# gate_driver.net
KiCad netlist of a schematic drawn in EAGLE
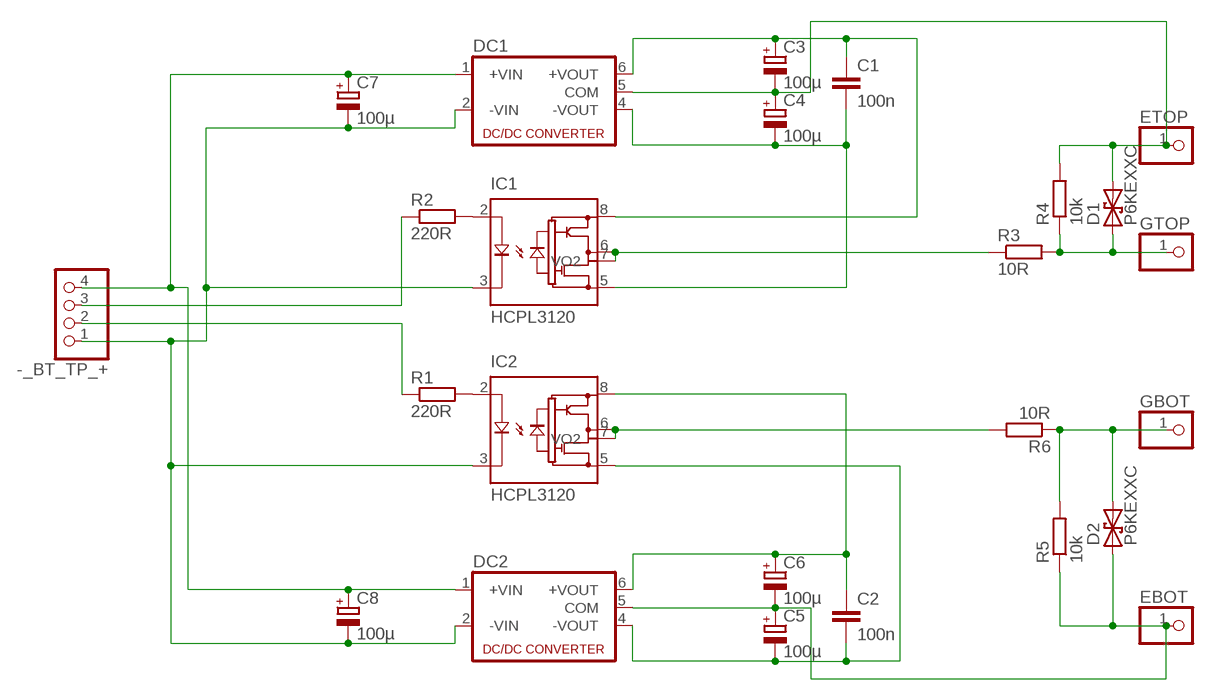
[diagram p0: schematic, sheet 1]

(export (version "E")
  (design (tool "Eeschema 10.0.6"))
  (components
    (comp (ref "-_BT_TP_+")
      (value "PINHD-1X4")
      (footprint "eagle-import:1X04")
      (libsource (lib "eagle-import") (part "PINHD-1X4"))
    )
    (comp (ref "C1")
      (value "100n")
      (footprint "eagle-import:C050-025X075")
      (libsource (lib "eagle-import") (part "C-EU050-025X075"))
    )
    (comp (ref "C2")
      (value "100n")
      (footprint "eagle-import:C050-025X075")
      (libsource (lib "eagle-import") (part "C-EU050-025X075"))
    )
    (comp (ref "C3")
      (value "100µ")
      (footprint "eagle-import:E2,5-6E")
      (libsource (lib "eagle-import") (part "CPOL-EUE2,5-6E"))
    )
    (comp (ref "C4")
      (value "100µ")
      (footprint "eagle-import:E2,5-6E")
      (libsource (lib "eagle-import") (part "CPOL-EUE2,5-6E"))
    )
    (comp (ref "C5")
      (value "100µ")
      (footprint "eagle-import:E2,5-6E")
      (libsource (lib "eagle-import") (part "CPOL-EUE2,5-6E"))
    )
    (comp (ref "C6")
      (value "100µ")
      (footprint "eagle-import:E2,5-6E")
      (libsource (lib "eagle-import") (part "CPOL-EUE2,5-6E"))
    )
    (comp (ref "C7")
      (value "100µ")
      (footprint "eagle-import:E2,5-5")
      (libsource (lib "eagle-import") (part "CPOL-EUE2.5-5"))
    )
    (comp (ref "C8")
      (value "100µ")
      (footprint "eagle-import:E2,5-5")
      (libsource (lib "eagle-import") (part "CPOL-EUE2.5-5"))
    )
    (comp (ref "D1")
      (value "P6KEXXC")
      (footprint "eagle-import:CB417-15")
      (libsource (lib "eagle-import") (part "P6KEXXC"))
    )
    (comp (ref "D2")
      (value "P6KEXXC")
      (footprint "eagle-import:CB417-15")
      (libsource (lib "eagle-import") (part "P6KEXXC"))
    )
    (comp (ref "DC1")
      (value "NMA")
      (footprint "eagle-import:NMA")
      (libsource (lib "eagle-import") (part "NMA"))
    )
    (comp (ref "DC2")
      (value "NMA")
      (footprint "eagle-import:NMA")
      (libsource (lib "eagle-import") (part "NMA"))
    )
    (comp (ref "EBOT")
      (value "PINHD-1X1")
      (footprint "eagle-import:1X01")
      (libsource (lib "eagle-import") (part "PINHD-1X1"))
    )
    (comp (ref "ETOP")
      (value "PINHD-1X1")
      (footprint "eagle-import:1X01")
      (libsource (lib "eagle-import") (part "PINHD-1X1"))
    )
    (comp (ref "GBOT")
      (value "PINHD-1X1")
      (footprint "eagle-import:1X01")
      (libsource (lib "eagle-import") (part "PINHD-1X1"))
    )
    (comp (ref "GTOP")
      (value "PINHD-1X1")
      (footprint "eagle-import:1X01")
      (libsource (lib "eagle-import") (part "PINHD-1X1"))
    )
    (comp (ref "IC1")
      (value "HCPL3120")
      (footprint "eagle-import:DIL08")
      (libsource (lib "eagle-import") (part "HCPL3120"))
    )
    (comp (ref "IC2")
      (value "HCPL3120")
      (footprint "eagle-import:DIL08")
      (libsource (lib "eagle-import") (part "HCPL3120"))
    )
    (comp (ref "R1")
      (value "220R")
      (footprint "eagle-import:0207_10")
      (libsource (lib "eagle-import") (part "R-EU_0207/10"))
    )
    (comp (ref "R2")
      (value "220R")
      (footprint "eagle-import:0207_10")
      (libsource (lib "eagle-import") (part "R-EU_0207/10"))
    )
    (comp (ref "R3")
      (value "10R")
      (footprint "eagle-import:0309_12")
      (libsource (lib "eagle-import") (part "R-EU_0309/12"))
    )
    (comp (ref "R4")
      (value "10k")
      (footprint "eagle-import:0207_10")
      (libsource (lib "eagle-import") (part "R-EU_0207/10"))
    )
    (comp (ref "R5")
      (value "10k")
      (footprint "eagle-import:0207_10")
      (libsource (lib "eagle-import") (part "R-EU_0207/10"))
    )
    (comp (ref "R6")
      (value "10R")
      (footprint "eagle-import:0309_12")
      (libsource (lib "eagle-import") (part "R-EU_0309/12"))
    )
  )
  (nets
    (net (code "1") (name "Net-(-_BT_TP_+-Pad2)") (class "Default")
      (node (ref "-_BT_TP_+") (pin "2") (pinfunction "2_2") (pintype "passive"))
      (node (ref "R1") (pin "1") (pinfunction "1_1") (pintype "passive"))
    )
    (net (code "2") (name "Net-(-_BT_TP_+-Pad3)") (class "Default")
      (node (ref "-_BT_TP_+") (pin "3") (pinfunction "3_3") (pintype "passive"))
      (node (ref "R2") (pin "1") (pinfunction "1_1") (pintype "passive"))
    )
    (net (code "3") (name "Net-(D1-1)") (class "Default")
      (node (ref "D1") (pin "A") (pinfunction "1_A") (pintype "passive"))
      (node (ref "GTOP") (pin "1") (pinfunction "1_1") (pintype "passive"))
      (node (ref "R3") (pin "2") (pinfunction "2_2") (pintype "passive"))
      (node (ref "R4") (pin "1") (pinfunction "1_1") (pintype "passive"))
    )
    (net (code "4") (name "Net-(D1-2)") (class "Default")
      (node (ref "C3") (pin "-") (pinfunction "-_-") (pintype "passive"))
      (node (ref "C4") (pin "+") (pinfunction "+_+") (pintype "passive"))
      (node (ref "D1") (pin "C") (pinfunction "2_C") (pintype "passive"))
      (node (ref "DC1") (pin "5") (pinfunction "COM_5") (pintype "passive"))
      (node (ref "ETOP") (pin "1") (pinfunction "1_1") (pintype "passive"))
      (node (ref "R4") (pin "2") (pinfunction "2_2") (pintype "passive"))
    )
    (net (code "5") (name "Net-(D2-1)") (class "Default")
      (node (ref "C5") (pin "+") (pinfunction "+_+") (pintype "passive"))
      (node (ref "C6") (pin "-") (pinfunction "-_-") (pintype "passive"))
      (node (ref "D2") (pin "A") (pinfunction "1_A") (pintype "passive"))
      (node (ref "DC2") (pin "5") (pinfunction "COM_5") (pintype "passive"))
      (node (ref "EBOT") (pin "1") (pinfunction "1_1") (pintype "passive"))
      (node (ref "R5") (pin "1") (pinfunction "1_1") (pintype "passive"))
    )
    (net (code "6") (name "Net-(D2-2)") (class "Default")
      (node (ref "D2") (pin "C") (pinfunction "2_C") (pintype "passive"))
      (node (ref "GBOT") (pin "1") (pinfunction "1_1") (pintype "passive"))
      (node (ref "R5") (pin "2") (pinfunction "2_2") (pintype "passive"))
      (node (ref "R6") (pin "1") (pinfunction "1_1") (pintype "passive"))
    )
    (net (code "7") (name "Net-(DC1-+VIN)") (class "Default")
      (node (ref "-_BT_TP_+") (pin "4") (pinfunction "4_4") (pintype "passive"))
      (node (ref "C7") (pin "+") (pinfunction "+_+") (pintype "passive"))
      (node (ref "C8") (pin "+") (pinfunction "+_+") (pintype "passive"))
      (node (ref "DC1") (pin "1") (pinfunction "+VIN_1") (pintype "passive"))
      (node (ref "DC2") (pin "1") (pinfunction "+VIN_1") (pintype "passive"))
    )
    (net (code "8") (name "Net-(DC1-+VOUT)") (class "Default")
      (node (ref "C1") (pin "1") (pinfunction "1_1") (pintype "passive"))
      (node (ref "C3") (pin "+") (pinfunction "+_+") (pintype "passive"))
      (node (ref "DC1") (pin "6") (pinfunction "+VOUT_6") (pintype "passive"))
      (node (ref "IC1") (pin "8") (pinfunction "VCC_8") (pintype "passive"))
    )
    (net (code "9") (name "Net-(DC1--VIN)") (class "Default")
      (node (ref "-_BT_TP_+") (pin "1") (pinfunction "1_1") (pintype "passive"))
      (node (ref "C7") (pin "-") (pinfunction "-_-") (pintype "passive"))
      (node (ref "C8") (pin "-") (pinfunction "-_-") (pintype "passive"))
      (node (ref "DC1") (pin "2") (pinfunction "-VIN_2") (pintype "passive"))
      (node (ref "DC2") (pin "2") (pinfunction "-VIN_2") (pintype "passive"))
      (node (ref "IC1") (pin "3") (pinfunction "CATHODE_3") (pintype "passive"))
      (node (ref "IC2") (pin "3") (pinfunction "CATHODE_3") (pintype "passive"))
    )
    (net (code "10") (name "Net-(DC1--VOUT)") (class "Default")
      (node (ref "C1") (pin "2") (pinfunction "2_2") (pintype "passive"))
      (node (ref "C4") (pin "-") (pinfunction "-_-") (pintype "passive"))
      (node (ref "DC1") (pin "4") (pinfunction "-VOUT_4") (pintype "passive"))
      (node (ref "IC1") (pin "5") (pinfunction "VEE_5") (pintype "passive"))
    )
    (net (code "11") (name "Net-(DC2-+VOUT)") (class "Default")
      (node (ref "C2") (pin "1") (pinfunction "1_1") (pintype "passive"))
      (node (ref "C6") (pin "+") (pinfunction "+_+") (pintype "passive"))
      (node (ref "DC2") (pin "6") (pinfunction "+VOUT_6") (pintype "passive"))
      (node (ref "IC2") (pin "8") (pinfunction "VCC_8") (pintype "passive"))
    )
    (net (code "12") (name "Net-(DC2--VOUT)") (class "Default")
      (node (ref "C2") (pin "2") (pinfunction "2_2") (pintype "passive"))
      (node (ref "C5") (pin "-") (pinfunction "-_-") (pintype "passive"))
      (node (ref "DC2") (pin "4") (pinfunction "-VOUT_4") (pintype "passive"))
      (node (ref "IC2") (pin "5") (pinfunction "VEE_5") (pintype "passive"))
    )
    (net (code "13") (name "Net-(IC1-ANODE)") (class "Default")
      (node (ref "IC1") (pin "2") (pinfunction "ANODE_2") (pintype "passive"))
      (node (ref "R2") (pin "2") (pinfunction "2_2") (pintype "passive"))
    )
    (net (code "14") (name "Net-(IC1-VO)") (class "Default")
      (node (ref "IC1") (pin "6") (pinfunction "VO_6") (pintype "passive"))
      (node (ref "IC1") (pin "7") (pinfunction "VO2_7") (pintype "bidirectional"))
      (node (ref "R3") (pin "1") (pinfunction "1_1") (pintype "passive"))
    )
    (net (code "15") (name "Net-(IC2-ANODE)") (class "Default")
      (node (ref "IC2") (pin "2") (pinfunction "ANODE_2") (pintype "passive"))
      (node (ref "R1") (pin "2") (pinfunction "2_2") (pintype "passive"))
    )
    (net (code "16") (name "Net-(IC2-VO)") (class "Default")
      (node (ref "IC2") (pin "6") (pinfunction "VO_6") (pintype "passive"))
      (node (ref "IC2") (pin "7") (pinfunction "VO2_7") (pintype "bidirectional"))
      (node (ref "R6") (pin "2") (pinfunction "2_2") (pintype "passive"))
    )
  )
)
